# switch.net
KiCad netlist of a schematic drawn in Altium Designer
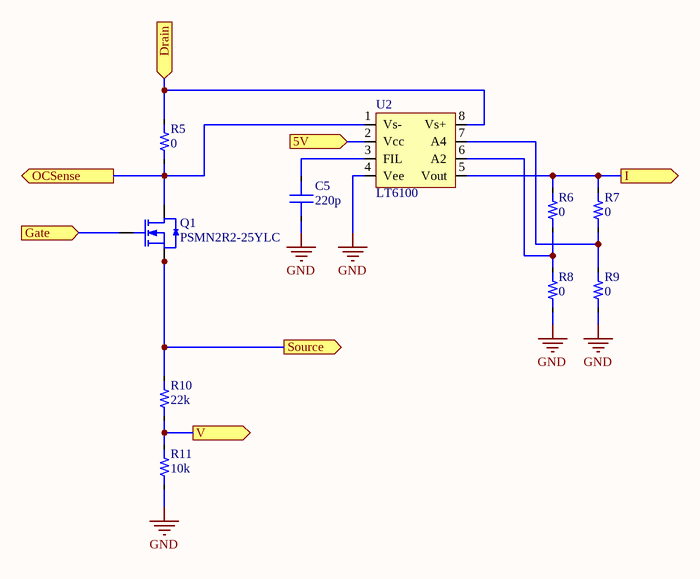
[diagram p0: switch.SchDoc]

(export (version "E")
  (design (tool "Eeschema 10.0.6"))
  (components
    (comp (ref "C5")
      (value "220p")
      (footprint "0603_CAP")
      (fields (field (name "Comment") "Capacitor"))
      (libsource (lib "Capacitors") (part "Capacitor"))
    )
    (comp (ref "Q1")
      (value "PSMN2R2-25YLC")
      (footprint "LFPAK-SO8")
      (description "N-channel 25 V 2.4 mΩ logic level MOSFET in LFPAK using NextPower")
      (libsource (lib "FETs") (part "PSMN2R2-25YLC"))
    )
    (comp (ref "R5")
      (value "0")
      (footprint "2010")
      (fields (field (name "Comment") "Resistor"))
      (libsource (lib "Resistors") (part "Resistor"))
    )
    (comp (ref "R6")
      (value "0")
      (footprint "0603_RES")
      (fields (field (name "Comment") "Resistor"))
      (libsource (lib "Resistors") (part "Resistor"))
    )
    (comp (ref "R7")
      (value "0")
      (footprint "0603_RES")
      (fields (field (name "Comment") "Resistor"))
      (libsource (lib "Resistors") (part "Resistor"))
    )
    (comp (ref "R8")
      (value "0")
      (footprint "0603_RES")
      (fields (field (name "Comment") "Resistor"))
      (libsource (lib "Resistors") (part "Resistor"))
    )
    (comp (ref "R9")
      (value "0")
      (footprint "0603_RES")
      (fields (field (name "Comment") "Resistor"))
      (libsource (lib "Resistors") (part "Resistor"))
    )
    (comp (ref "R10")
      (value "22k")
      (footprint "0603_RES")
      (fields (field (name "Comment") "Resistor"))
      (libsource (lib "Resistors") (part "Resistor"))
    )
    (comp (ref "R11")
      (value "10k")
      (footprint "0603_RES")
      (fields (field (name "Comment") "Resistor"))
      (libsource (lib "Resistors") (part "Resistor"))
    )
    (comp (ref "U2")
      (value "LT6100")
      (footprint "MSOP-8")
      (description "High Side Current Sense Amp")
      (libsource (lib "Analog_IC") (part "LT6100"))
    )
  )
  (nets
    (net (code "1") (name "/5V") (class "Default")
      (node (ref "U2") (pin "2") (pinfunction "Vcc_2") (pintype "passive"))
    )
    (net (code "2") (name "/Drain") (class "Default")
      (node (ref "R5") (pin "2") (pinfunction "2_2") (pintype "passive"))
      (node (ref "U2") (pin "8") (pinfunction "Vs+_8") (pintype "passive"))
    )
    (net (code "3") (name "/Gate") (class "Default")
      (node (ref "Q1") (pin "4") (pinfunction "G_4") (pintype "passive"))
    )
    (net (code "4") (name "/I") (class "Default")
      (node (ref "R6") (pin "2") (pinfunction "2_2") (pintype "passive"))
      (node (ref "R7") (pin "2") (pinfunction "2_2") (pintype "passive"))
      (node (ref "U2") (pin "5") (pinfunction "Vout_5") (pintype "passive"))
    )
    (net (code "5") (name "/OCSense") (class "Default")
      (node (ref "Q1") (pin "5") (pinfunction "D_5") (pintype "passive"))
      (node (ref "R5") (pin "1") (pinfunction "1_1") (pintype "passive"))
      (node (ref "U2") (pin "1") (pinfunction "Vs-_1") (pintype "passive"))
    )
    (net (code "6") (name "/Source") (class "Default")
      (node (ref "Q1") (pin "1") (pinfunction "S_1") (pintype "passive"))
      (node (ref "Q1") (pin "2") (pinfunction "S_2") (pintype "passive"))
      (node (ref "Q1") (pin "3") (pinfunction "S_3") (pintype "passive"))
      (node (ref "R10") (pin "2") (pinfunction "2_2") (pintype "passive"))
    )
    (net (code "7") (name "/V") (class "Default")
      (node (ref "R10") (pin "1") (pinfunction "1_1") (pintype "passive"))
      (node (ref "R11") (pin "2") (pinfunction "2_2") (pintype "passive"))
    )
    (net (code "8") (name "GND") (class "Default")
      (node (ref "C5") (pin "1") (pinfunction "1_1") (pintype "passive"))
      (node (ref "R11") (pin "1") (pinfunction "1_1") (pintype "passive"))
      (node (ref "R8") (pin "1") (pinfunction "1_1") (pintype "passive"))
      (node (ref "R9") (pin "1") (pinfunction "1_1") (pintype "passive"))
      (node (ref "U2") (pin "4") (pinfunction "Vee_4") (pintype "passive"))
    )
    (net (code "9") (name "Net-(U2-A2)") (class "Default")
      (node (ref "R6") (pin "1") (pinfunction "1_1") (pintype "passive"))
      (node (ref "R8") (pin "2") (pinfunction "2_2") (pintype "passive"))
      (node (ref "U2") (pin "6") (pinfunction "A2_6") (pintype "passive"))
    )
    (net (code "10") (name "Net-(U2-A4)") (class "Default")
      (node (ref "R7") (pin "1") (pinfunction "1_1") (pintype "passive"))
      (node (ref "R9") (pin "2") (pinfunction "2_2") (pintype "passive"))
      (node (ref "U2") (pin "7") (pinfunction "A4_7") (pintype "passive"))
    )
    (net (code "11") (name "Net-(U2-FIL)") (class "Default")
      (node (ref "C5") (pin "2") (pinfunction "2_2") (pintype "passive"))
      (node (ref "U2") (pin "3") (pinfunction "FIL_3") (pintype "passive"))
    )
  )
)
